# dmx_splitter.net
KiCad netlist of a schematic drawn in EAGLE
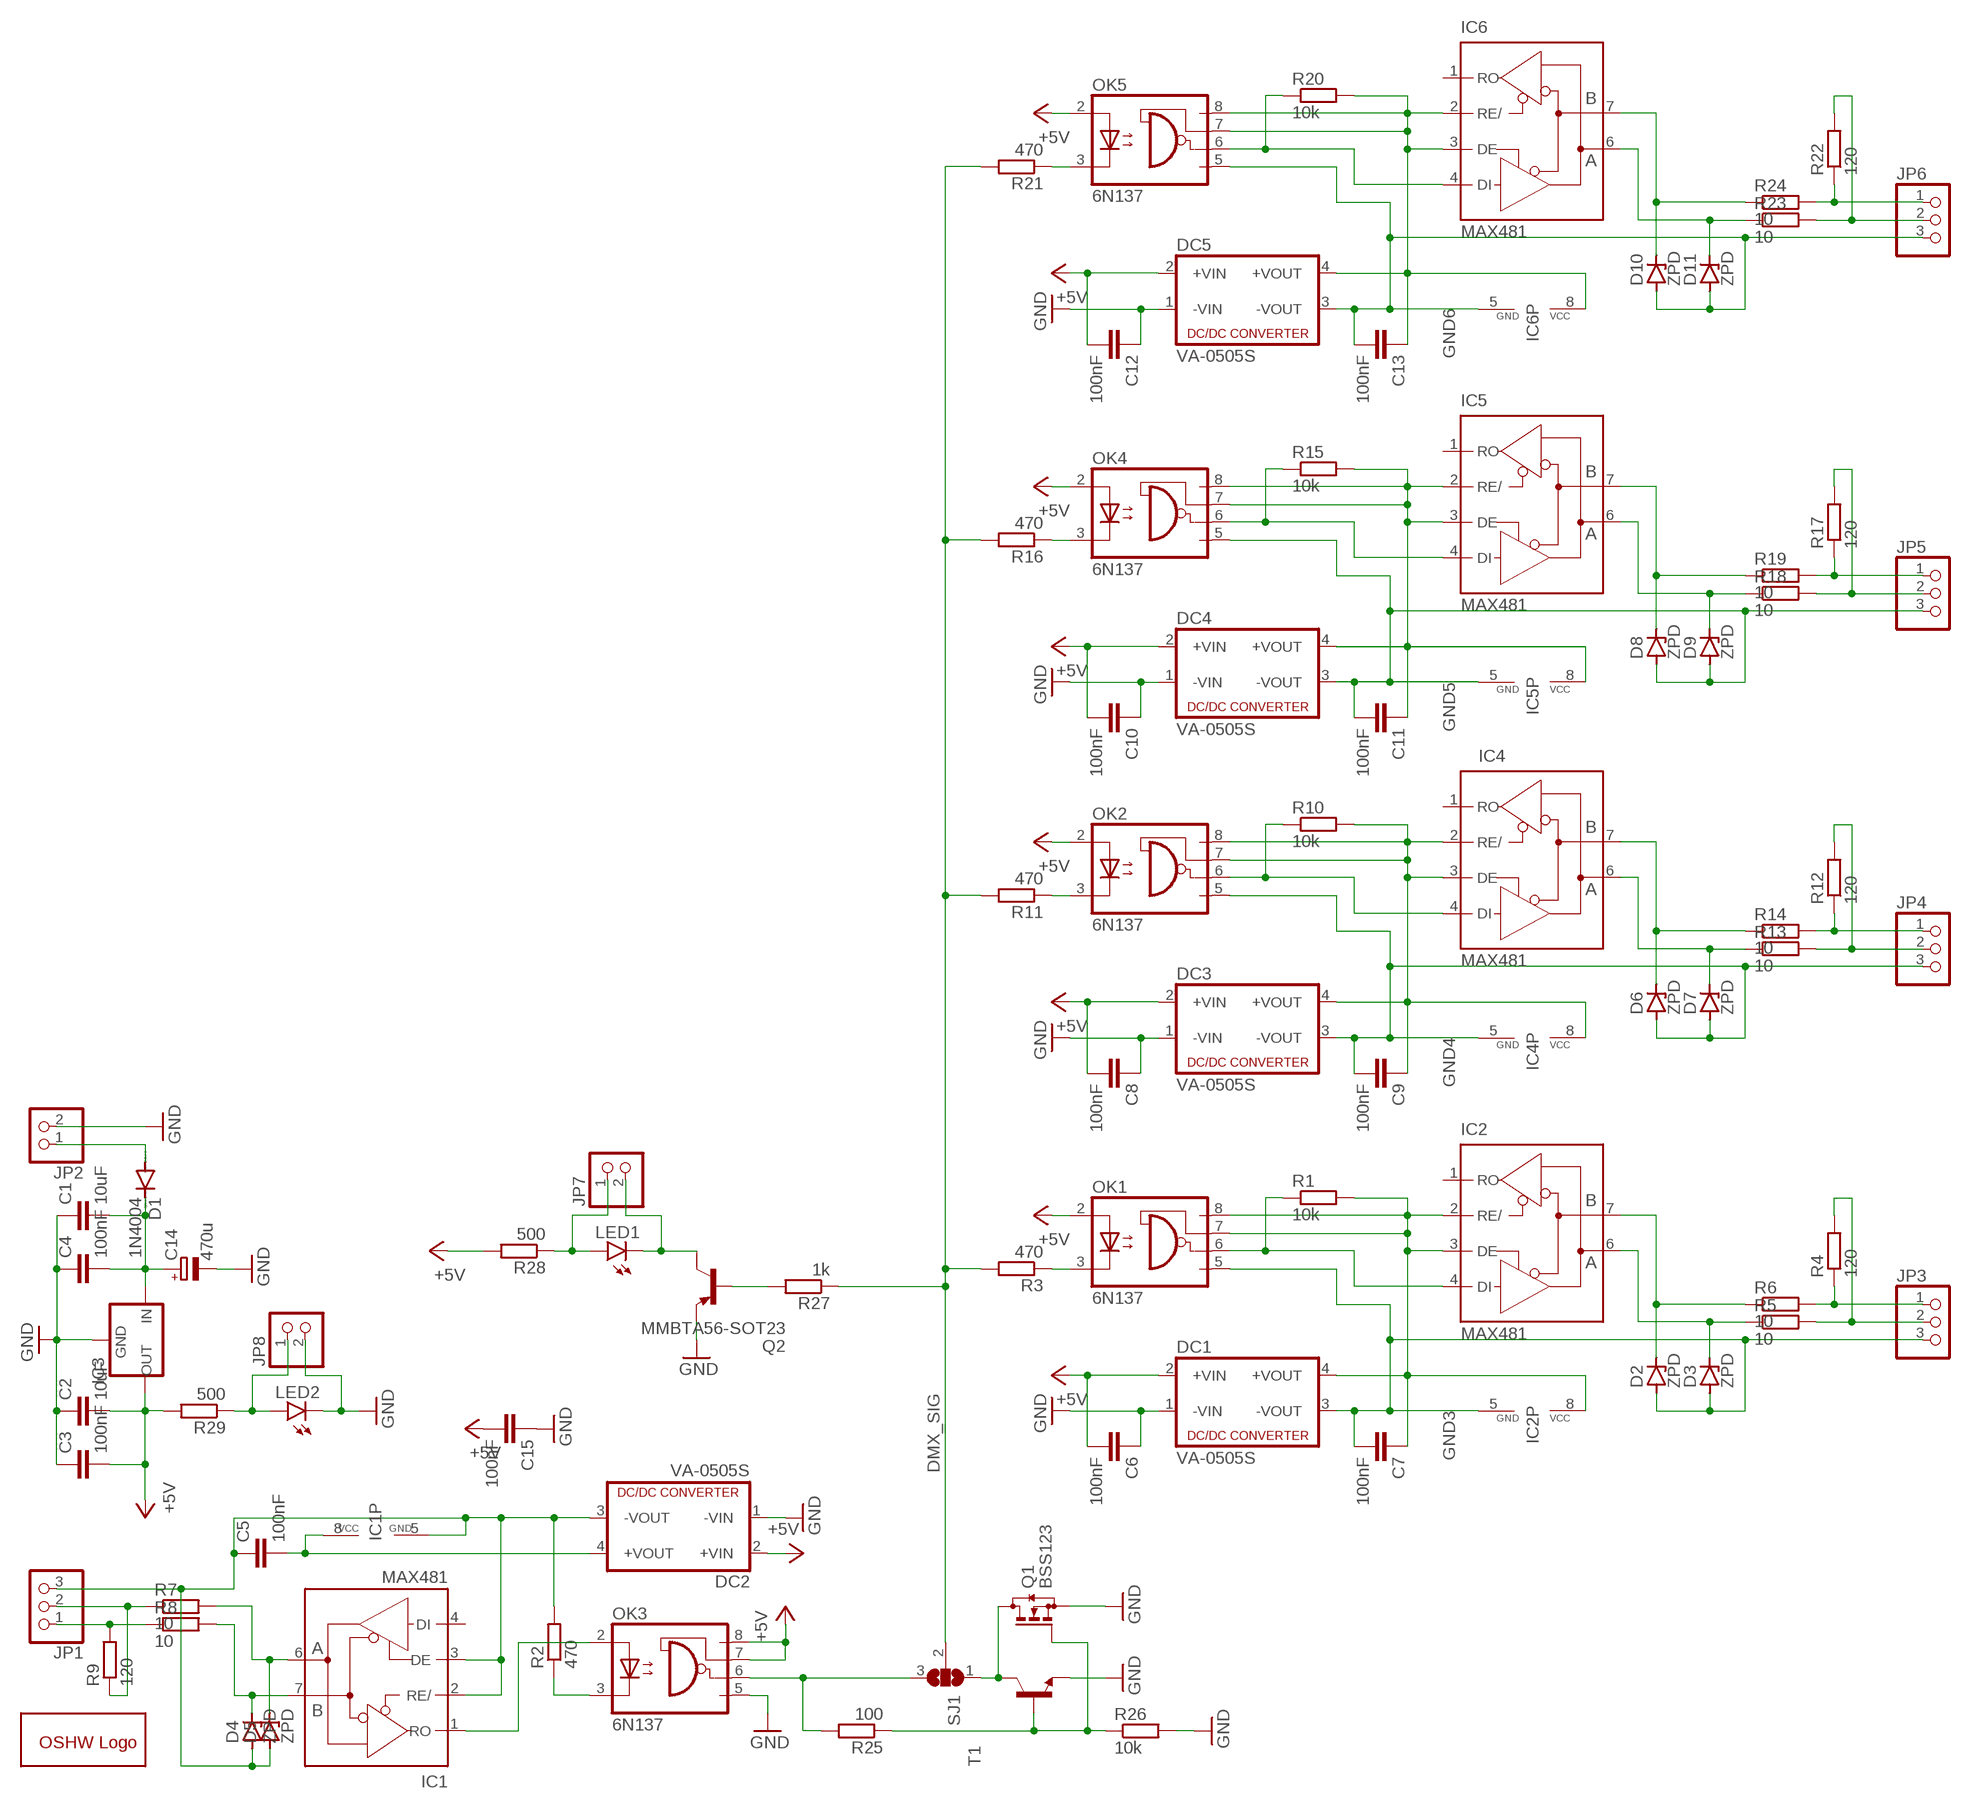
[diagram p0: schematic, sheet 1]

(export (version "E")
  (design (tool "Eeschema 10.0.6"))
  (components
    (comp (ref "C1")
      (value "10uF")
      (footprint "eagle-import:C1206")
      (libsource (lib "eagle-import") (part "C-EUC1206"))
    )
    (comp (ref "C2")
      (value "10uF")
      (footprint "eagle-import:C1206")
      (libsource (lib "eagle-import") (part "C-EUC1206"))
    )
    (comp (ref "C3")
      (value "100nF")
      (footprint "eagle-import:C1206")
      (libsource (lib "eagle-import") (part "C-EUC1206"))
    )
    (comp (ref "C4")
      (value "100nF")
      (footprint "eagle-import:C1206")
      (libsource (lib "eagle-import") (part "C-EUC1206"))
    )
    (comp (ref "C5")
      (value "100nF")
      (footprint "eagle-import:C1206")
      (libsource (lib "eagle-import") (part "C-EUC1206"))
    )
    (comp (ref "C6")
      (value "100nF")
      (footprint "eagle-import:C1206")
      (libsource (lib "eagle-import") (part "C-EUC1206"))
    )
    (comp (ref "C7")
      (value "100nF")
      (footprint "eagle-import:C1206")
      (libsource (lib "eagle-import") (part "C-EUC1206"))
    )
    (comp (ref "C8")
      (value "100nF")
      (footprint "eagle-import:C1206")
      (libsource (lib "eagle-import") (part "C-EUC1206"))
    )
    (comp (ref "C9")
      (value "100nF")
      (footprint "eagle-import:C1206")
      (libsource (lib "eagle-import") (part "C-EUC1206"))
    )
    (comp (ref "C10")
      (value "100nF")
      (footprint "eagle-import:C1206")
      (libsource (lib "eagle-import") (part "C-EUC1206"))
    )
    (comp (ref "C11")
      (value "100nF")
      (footprint "eagle-import:C1206")
      (libsource (lib "eagle-import") (part "C-EUC1206"))
    )
    (comp (ref "C12")
      (value "100nF")
      (footprint "eagle-import:C1206")
      (libsource (lib "eagle-import") (part "C-EUC1206"))
    )
    (comp (ref "C13")
      (value "100nF")
      (footprint "eagle-import:C1206")
      (libsource (lib "eagle-import") (part "C-EUC1206"))
    )
    (comp (ref "C14")
      (value "470u")
      (footprint "eagle-import:E2,5-7")
      (libsource (lib "eagle-import") (part "CPOL-EUE2.5-7"))
    )
    (comp (ref "C15")
      (value "100nF")
      (footprint "eagle-import:C1206")
      (libsource (lib "eagle-import") (part "C-EUC1206"))
    )
    (comp (ref "D1")
      (value "1N4004")
      (footprint "eagle-import:DO41-10")
      (libsource (lib "eagle-import") (part "1N4004"))
    )
    (comp (ref "D2")
      (value "ZPD")
      (footprint "eagle-import:DO35Z10")
      (libsource (lib "eagle-import") (part "ZPD"))
    )
    (comp (ref "D3")
      (value "ZPD")
      (footprint "eagle-import:DO35Z10")
      (libsource (lib "eagle-import") (part "ZPD"))
    )
    (comp (ref "D4")
      (value "ZPD")
      (footprint "eagle-import:DO35Z10")
      (libsource (lib "eagle-import") (part "ZPD"))
    )
    (comp (ref "D5")
      (value "ZPD")
      (footprint "eagle-import:DO35Z10")
      (libsource (lib "eagle-import") (part "ZPD"))
    )
    (comp (ref "D6")
      (value "ZPD")
      (footprint "eagle-import:DO35Z10")
      (libsource (lib "eagle-import") (part "ZPD"))
    )
    (comp (ref "D7")
      (value "ZPD")
      (footprint "eagle-import:DO35Z10")
      (libsource (lib "eagle-import") (part "ZPD"))
    )
    (comp (ref "D8")
      (value "ZPD")
      (footprint "eagle-import:DO35Z10")
      (libsource (lib "eagle-import") (part "ZPD"))
    )
    (comp (ref "D9")
      (value "ZPD")
      (footprint "eagle-import:DO35Z10")
      (libsource (lib "eagle-import") (part "ZPD"))
    )
    (comp (ref "D10")
      (value "ZPD")
      (footprint "eagle-import:DO35Z10")
      (libsource (lib "eagle-import") (part "ZPD"))
    )
    (comp (ref "D11")
      (value "ZPD")
      (footprint "eagle-import:DO35Z10")
      (libsource (lib "eagle-import") (part "ZPD"))
    )
    (comp (ref "DC1")
      (value "VA-0505S")
      (footprint "eagle-import:4SIL")
      (libsource (lib "eagle-import") (part "VA-?S0505"))
    )
    (comp (ref "DC2")
      (value "VA-0505S")
      (footprint "eagle-import:4SIL")
      (libsource (lib "eagle-import") (part "VA-?S0505"))
    )
    (comp (ref "DC3")
      (value "VA-0505S")
      (footprint "eagle-import:4SIL")
      (libsource (lib "eagle-import") (part "VA-?S0505"))
    )
    (comp (ref "DC4")
      (value "VA-0505S")
      (footprint "eagle-import:4SIL")
      (libsource (lib "eagle-import") (part "VA-?S0505"))
    )
    (comp (ref "DC5")
      (value "VA-0505S")
      (footprint "eagle-import:4SIL")
      (libsource (lib "eagle-import") (part "VA-?S0505"))
    )
    (comp (ref "GOLD_ORB_SM1")
      (value "OSHWLOGOLOGO5MM")
      (footprint "eagle-import:OSHW_5MM")
      (libsource (lib "eagle-import") (part "OSHWLOGOLOGO5MM"))
    )
    (comp (ref "IC1")
      (value "MAX481")
      (footprint "eagle-import:DIL08")
      (libsource (lib "eagle-import") (part "MAX481CPA"))
    )
    (comp (ref "IC2")
      (value "MAX481")
      (footprint "eagle-import:DIL08")
      (libsource (lib "eagle-import") (part "MAX481CPA"))
    )
    (comp (ref "IC3")
      (value "78XXS")
      (footprint "eagle-import:78XXS")
      (libsource (lib "eagle-import") (part "78XXS"))
    )
    (comp (ref "IC4")
      (value "MAX481")
      (footprint "eagle-import:DIL08")
      (libsource (lib "eagle-import") (part "MAX481CPA"))
    )
    (comp (ref "IC5")
      (value "MAX481")
      (footprint "eagle-import:DIL08")
      (libsource (lib "eagle-import") (part "MAX481CPA"))
    )
    (comp (ref "IC6")
      (value "MAX481")
      (footprint "eagle-import:DIL08")
      (libsource (lib "eagle-import") (part "MAX481CPA"))
    )
    (comp (ref "JP1")
      (value "PINHD-1X3")
      (footprint "eagle-import:1X03")
      (libsource (lib "eagle-import") (part "PINHD-1X3"))
    )
    (comp (ref "JP2")
      (value "PINHD-1X2")
      (footprint "eagle-import:1X02")
      (libsource (lib "eagle-import") (part "PINHD-1X2"))
    )
    (comp (ref "JP3")
      (value "PINHD-1X3")
      (footprint "eagle-import:1X03")
      (libsource (lib "eagle-import") (part "PINHD-1X3"))
    )
    (comp (ref "JP4")
      (value "PINHD-1X3")
      (footprint "eagle-import:1X03")
      (libsource (lib "eagle-import") (part "PINHD-1X3"))
    )
    (comp (ref "JP5")
      (value "PINHD-1X3")
      (footprint "eagle-import:1X03")
      (libsource (lib "eagle-import") (part "PINHD-1X3"))
    )
    (comp (ref "JP6")
      (value "PINHD-1X3")
      (footprint "eagle-import:1X03")
      (libsource (lib "eagle-import") (part "PINHD-1X3"))
    )
    (comp (ref "JP7")
      (value "PINHD-1X2")
      (footprint "eagle-import:1X02")
      (libsource (lib "eagle-import") (part "PINHD-1X2"))
    )
    (comp (ref "JP8")
      (value "PINHD-1X2")
      (footprint "eagle-import:1X02")
      (libsource (lib "eagle-import") (part "PINHD-1X2"))
    )
    (comp (ref "LED1")
      (value "LEDCHIPLED_1206")
      (footprint "eagle-import:CHIPLED_1206")
      (libsource (lib "eagle-import") (part "LEDCHIPLED_1206"))
    )
    (comp (ref "LED2")
      (value "LEDCHIPLED_1206")
      (footprint "eagle-import:CHIPLED_1206")
      (libsource (lib "eagle-import") (part "LEDCHIPLED_1206"))
    )
    (comp (ref "OK1")
      (value "6N137")
      (footprint "eagle-import:DIL08")
      (libsource (lib "eagle-import") (part "6N137"))
    )
    (comp (ref "OK2")
      (value "6N137")
      (footprint "eagle-import:DIL08")
      (libsource (lib "eagle-import") (part "6N137"))
    )
    (comp (ref "OK3")
      (value "6N137")
      (footprint "eagle-import:DIL08")
      (libsource (lib "eagle-import") (part "6N137"))
    )
    (comp (ref "OK4")
      (value "6N137")
      (footprint "eagle-import:DIL08")
      (libsource (lib "eagle-import") (part "6N137"))
    )
    (comp (ref "OK5")
      (value "6N137")
      (footprint "eagle-import:DIL08")
      (libsource (lib "eagle-import") (part "6N137"))
    )
    (comp (ref "Q1")
      (value "BSS123")
      (footprint "eagle-import:SOT23")
      (libsource (lib "eagle-import") (part "BSS123"))
    )
    (comp (ref "Q2")
      (value "MMBTA56-SOT23")
      (footprint "eagle-import:SOT23")
      (libsource (lib "eagle-import") (part "-?SOT23MMBTA56"))
    )
    (comp (ref "R1")
      (value "10k")
      (footprint "eagle-import:R1206")
      (libsource (lib "eagle-import") (part "R-EU_R1206"))
    )
    (comp (ref "R2")
      (value "470")
      (footprint "eagle-import:R1206")
      (libsource (lib "eagle-import") (part "R-EU_R1206"))
    )
    (comp (ref "R3")
      (value "470")
      (footprint "eagle-import:R1206")
      (libsource (lib "eagle-import") (part "R-EU_R1206"))
    )
    (comp (ref "R4")
      (value "120")
      (footprint "eagle-import:R1206")
      (libsource (lib "eagle-import") (part "R-EU_R1206"))
    )
    (comp (ref "R5")
      (value "10")
      (footprint "eagle-import:R1206")
      (libsource (lib "eagle-import") (part "R-EU_R1206"))
    )
    (comp (ref "R6")
      (value "10")
      (footprint "eagle-import:R1206")
      (libsource (lib "eagle-import") (part "R-EU_R1206"))
    )
    (comp (ref "R7")
      (value "10")
      (footprint "eagle-import:R1206")
      (libsource (lib "eagle-import") (part "R-EU_R1206"))
    )
    (comp (ref "R8")
      (value "10")
      (footprint "eagle-import:R1206")
      (libsource (lib "eagle-import") (part "R-EU_R1206"))
    )
    (comp (ref "R9")
      (value "120")
      (footprint "eagle-import:R1206")
      (libsource (lib "eagle-import") (part "R-EU_R1206"))
    )
    (comp (ref "R10")
      (value "10k")
      (footprint "eagle-import:R1206")
      (libsource (lib "eagle-import") (part "R-EU_R1206"))
    )
    (comp (ref "R11")
      (value "470")
      (footprint "eagle-import:R1206")
      (libsource (lib "eagle-import") (part "R-EU_R1206"))
    )
    (comp (ref "R12")
      (value "120")
      (footprint "eagle-import:R1206")
      (libsource (lib "eagle-import") (part "R-EU_R1206"))
    )
    (comp (ref "R13")
      (value "10")
      (footprint "eagle-import:R1206")
      (libsource (lib "eagle-import") (part "R-EU_R1206"))
    )
    (comp (ref "R14")
      (value "10")
      (footprint "eagle-import:R1206")
      (libsource (lib "eagle-import") (part "R-EU_R1206"))
    )
    (comp (ref "R15")
      (value "10k")
      (footprint "eagle-import:R1206")
      (libsource (lib "eagle-import") (part "R-EU_R1206"))
    )
    (comp (ref "R16")
      (value "470")
      (footprint "eagle-import:R1206")
      (libsource (lib "eagle-import") (part "R-EU_R1206"))
    )
    (comp (ref "R17")
      (value "120")
      (footprint "eagle-import:R1206")
      (libsource (lib "eagle-import") (part "R-EU_R1206"))
    )
    (comp (ref "R18")
      (value "10")
      (footprint "eagle-import:R1206")
      (libsource (lib "eagle-import") (part "R-EU_R1206"))
    )
    (comp (ref "R19")
      (value "10")
      (footprint "eagle-import:R1206")
      (libsource (lib "eagle-import") (part "R-EU_R1206"))
    )
    (comp (ref "R20")
      (value "10k")
      (footprint "eagle-import:R1206")
      (libsource (lib "eagle-import") (part "R-EU_R1206"))
    )
    (comp (ref "R21")
      (value "470")
      (footprint "eagle-import:R1206")
      (libsource (lib "eagle-import") (part "R-EU_R1206"))
    )
    (comp (ref "R22")
      (value "120")
      (footprint "eagle-import:R1206")
      (libsource (lib "eagle-import") (part "R-EU_R1206"))
    )
    (comp (ref "R23")
      (value "10")
      (footprint "eagle-import:R1206")
      (libsource (lib "eagle-import") (part "R-EU_R1206"))
    )
    (comp (ref "R24")
      (value "10")
      (footprint "eagle-import:R1206")
      (libsource (lib "eagle-import") (part "R-EU_R1206"))
    )
    (comp (ref "R25")
      (value "100")
      (footprint "eagle-import:R1206")
      (libsource (lib "eagle-import") (part "R-EU_R1206"))
    )
    (comp (ref "R26")
      (value "10k")
      (footprint "eagle-import:R1206")
      (libsource (lib "eagle-import") (part "R-EU_R1206"))
    )
    (comp (ref "R27")
      (value "1k")
      (footprint "eagle-import:R1206")
      (libsource (lib "eagle-import") (part "R-EU_R1206"))
    )
    (comp (ref "R28")
      (value "500")
      (footprint "eagle-import:R1206")
      (libsource (lib "eagle-import") (part "R-EU_R1206"))
    )
    (comp (ref "R29")
      (value "500")
      (footprint "eagle-import:R1206")
      (libsource (lib "eagle-import") (part "R-EU_R1206"))
    )
    (comp (ref "SJ1")
      (value "SJ2W")
      (footprint "eagle-import:SJ_2")
      (libsource (lib "eagle-import") (part "SJ2W"))
    )
    (comp (ref "T1")
      (value "-NPN-SOT23-EBC")
      (footprint "eagle-import:SOT23-EBC")
      (libsource (lib "eagle-import") (part "-NPN-SOT23-EBC"))
    )
  )
  (nets
    (net (code "1") (name "+5V") (class "Default")
      (node (ref "C10") (pin "2") (pinfunction "2_2") (pintype "passive"))
      (node (ref "C12") (pin "2") (pinfunction "2_2") (pintype "passive"))
      (node (ref "C15") (pin "2") (pinfunction "2_2") (pintype "passive"))
      (node (ref "C2") (pin "2") (pinfunction "2_2") (pintype "passive"))
      (node (ref "C3") (pin "2") (pinfunction "2_2") (pintype "passive"))
      (node (ref "C6") (pin "2") (pinfunction "2_2") (pintype "passive"))
      (node (ref "C8") (pin "2") (pinfunction "2_2") (pintype "passive"))
      (node (ref "DC1") (pin "2") (pinfunction "+VIN_2") (pintype "passive"))
      (node (ref "DC2") (pin "2") (pinfunction "+VIN_2") (pintype "passive"))
      (node (ref "DC3") (pin "2") (pinfunction "+VIN_2") (pintype "passive"))
      (node (ref "DC4") (pin "2") (pinfunction "+VIN_2") (pintype "passive"))
      (node (ref "DC5") (pin "2") (pinfunction "+VIN_2") (pintype "passive"))
      (node (ref "IC3") (pin "OUT") (pinfunction "OUT_OUT") (pintype "passive"))
      (node (ref "OK1") (pin "2") (pinfunction "A_2") (pintype "passive"))
      (node (ref "OK2") (pin "2") (pinfunction "A_2") (pintype "passive"))
      (node (ref "OK3") (pin "7") (pinfunction "VE_7") (pintype "passive"))
      (node (ref "OK3") (pin "8") (pinfunction "VCC_8") (pintype "passive"))
      (node (ref "OK4") (pin "2") (pinfunction "A_2") (pintype "passive"))
      (node (ref "OK5") (pin "2") (pinfunction "A_2") (pintype "passive"))
      (node (ref "R28") (pin "2") (pinfunction "2_2") (pintype "passive"))
      (node (ref "R29") (pin "2") (pinfunction "2_2") (pintype "passive"))
    )
    (net (code "2") (name "/DMX_SIG") (class "Default")
      (node (ref "R11") (pin "2") (pinfunction "2_2") (pintype "passive"))
      (node (ref "R16") (pin "2") (pinfunction "2_2") (pintype "passive"))
      (node (ref "R21") (pin "2") (pinfunction "2_2") (pintype "passive"))
      (node (ref "R27") (pin "1") (pinfunction "1_1") (pintype "passive"))
      (node (ref "R3") (pin "2") (pinfunction "2_2") (pintype "passive"))
      (node (ref "SJ1") (pin "2") (pinfunction "2_2") (pintype "passive"))
    )
    (net (code "3") (name "/GND3") (class "Default")
      (node (ref "C7") (pin "2") (pinfunction "2_2") (pintype "passive"))
      (node (ref "D2") (pin "A") (pinfunction "A_A") (pintype "passive"))
      (node (ref "D3") (pin "A") (pinfunction "A_A") (pintype "passive"))
      (node (ref "DC1") (pin "3") (pinfunction "-VOUT_3") (pintype "passive"))
      (node (ref "IC2") (pin "5") (pinfunction "GND_5") (pintype "power_in"))
      (node (ref "JP3") (pin "3") (pinfunction "3_3") (pintype "passive"))
      (node (ref "OK1") (pin "5") (pinfunction "GND_5") (pintype "passive"))
    )
    (net (code "4") (name "/GND4") (class "Default")
      (node (ref "C9") (pin "2") (pinfunction "2_2") (pintype "passive"))
      (node (ref "D6") (pin "A") (pinfunction "A_A") (pintype "passive"))
      (node (ref "D7") (pin "A") (pinfunction "A_A") (pintype "passive"))
      (node (ref "DC3") (pin "3") (pinfunction "-VOUT_3") (pintype "passive"))
      (node (ref "IC4") (pin "5") (pinfunction "GND_5") (pintype "power_in"))
      (node (ref "JP4") (pin "3") (pinfunction "3_3") (pintype "passive"))
      (node (ref "OK2") (pin "5") (pinfunction "GND_5") (pintype "passive"))
    )
    (net (code "5") (name "/GND5") (class "Default")
      (node (ref "C11") (pin "2") (pinfunction "2_2") (pintype "passive"))
      (node (ref "D8") (pin "A") (pinfunction "A_A") (pintype "passive"))
      (node (ref "D9") (pin "A") (pinfunction "A_A") (pintype "passive"))
      (node (ref "DC4") (pin "3") (pinfunction "-VOUT_3") (pintype "passive"))
      (node (ref "IC5") (pin "5") (pinfunction "GND_5") (pintype "power_in"))
      (node (ref "JP5") (pin "3") (pinfunction "3_3") (pintype "passive"))
      (node (ref "OK4") (pin "5") (pinfunction "GND_5") (pintype "passive"))
    )
    (net (code "6") (name "/GND6") (class "Default")
      (node (ref "C13") (pin "2") (pinfunction "2_2") (pintype "passive"))
      (node (ref "D10") (pin "A") (pinfunction "A_A") (pintype "passive"))
      (node (ref "D11") (pin "A") (pinfunction "A_A") (pintype "passive"))
      (node (ref "DC5") (pin "3") (pinfunction "-VOUT_3") (pintype "passive"))
      (node (ref "IC6") (pin "5") (pinfunction "GND_5") (pintype "power_in"))
      (node (ref "JP6") (pin "3") (pinfunction "3_3") (pintype "passive"))
      (node (ref "OK5") (pin "5") (pinfunction "GND_5") (pintype "passive"))
    )
    (net (code "7") (name "GND") (class "Default")
      (node (ref "C1") (pin "1") (pinfunction "1_1") (pintype "passive"))
      (node (ref "C10") (pin "1") (pinfunction "1_1") (pintype "passive"))
      (node (ref "C12") (pin "1") (pinfunction "1_1") (pintype "passive"))
      (node (ref "C14") (pin "-") (pinfunction "-_-") (pintype "passive"))
      (node (ref "C15") (pin "1") (pinfunction "1_1") (pintype "passive"))
      (node (ref "C2") (pin "1") (pinfunction "1_1") (pintype "passive"))
      (node (ref "C3") (pin "1") (pinfunction "1_1") (pintype "passive"))
      (node (ref "C4") (pin "1") (pinfunction "1_1") (pintype "passive"))
      (node (ref "C6") (pin "1") (pinfunction "1_1") (pintype "passive"))
      (node (ref "C8") (pin "1") (pinfunction "1_1") (pintype "passive"))
      (node (ref "DC1") (pin "1") (pinfunction "-VIN_1") (pintype "passive"))
      (node (ref "DC2") (pin "1") (pinfunction "-VIN_1") (pintype "passive"))
      (node (ref "DC3") (pin "1") (pinfunction "-VIN_1") (pintype "passive"))
      (node (ref "DC4") (pin "1") (pinfunction "-VIN_1") (pintype "passive"))
      (node (ref "DC5") (pin "1") (pinfunction "-VIN_1") (pintype "passive"))
      (node (ref "IC3") (pin "GND") (pinfunction "GND_GND") (pintype "input"))
      (node (ref "JP2") (pin "2") (pinfunction "2_2") (pintype "passive"))
      (node (ref "JP8") (pin "2") (pinfunction "2_2") (pintype "passive"))
      (node (ref "LED2") (pin "C") (pinfunction "C_C") (pintype "passive"))
      (node (ref "OK3") (pin "5") (pinfunction "GND_5") (pintype "passive"))
      (node (ref "Q1") (pin "2") (pinfunction "S_2") (pintype "passive"))
      (node (ref "Q2") (pin "2") (pinfunction "E_2") (pintype "passive"))
      (node (ref "R26") (pin "2") (pinfunction "2_2") (pintype "passive"))
      (node (ref "T1") (pin "E") (pinfunction "E_E") (pintype "passive"))
    )
    (net (code "8") (name "Net-(C1-Pad2)") (class "Default")
      (node (ref "C1") (pin "2") (pinfunction "2_2") (pintype "passive"))
      (node (ref "C14") (pin "+") (pinfunction "+_+") (pintype "passive"))
      (node (ref "C4") (pin "2") (pinfunction "2_2") (pintype "passive"))
      (node (ref "D1") (pin "C") (pinfunction "C_C") (pintype "passive"))
      (node (ref "IC3") (pin "IN") (pinfunction "IN_IN") (pintype "input"))
    )
    (net (code "9") (name "Net-(D1-PadA)") (class "Default")
      (node (ref "D1") (pin "A") (pinfunction "A_A") (pintype "passive"))
      (node (ref "JP2") (pin "1") (pinfunction "1_1") (pintype "passive"))
    )
    (net (code "10") (name "Net-(DC1-+VOUT)") (class "Default")
      (node (ref "C7") (pin "1") (pinfunction "1_1") (pintype "passive"))
      (node (ref "DC1") (pin "4") (pinfunction "+VOUT_4") (pintype "passive"))
      (node (ref "IC2") (pin "2") (pinfunction "RE/_2") (pintype "input"))
      (node (ref "IC2") (pin "3") (pinfunction "DE_3") (pintype "input"))
      (node (ref "IC2") (pin "8") (pinfunction "VCC_8") (pintype "power_in"))
      (node (ref "OK1") (pin "7") (pinfunction "VE_7") (pintype "passive"))
      (node (ref "OK1") (pin "8") (pinfunction "VCC_8") (pintype "passive"))
      (node (ref "R1") (pin "2") (pinfunction "2_2") (pintype "passive"))
    )
    (net (code "11") (name "Net-(DC2-+VOUT)") (class "Default")
      (node (ref "C5") (pin "2") (pinfunction "2_2") (pintype "passive"))
      (node (ref "DC2") (pin "4") (pinfunction "+VOUT_4") (pintype "passive"))
      (node (ref "IC1") (pin "8") (pinfunction "VCC_8") (pintype "power_in"))
    )
    (net (code "12") (name "Net-(DC2--VOUT)") (class "Default")
      (node (ref "C5") (pin "1") (pinfunction "1_1") (pintype "passive"))
      (node (ref "D4") (pin "A") (pinfunction "A_A") (pintype "passive"))
      (node (ref "D5") (pin "A") (pinfunction "A_A") (pintype "passive"))
      (node (ref "DC2") (pin "3") (pinfunction "-VOUT_3") (pintype "passive"))
      (node (ref "IC1") (pin "2") (pinfunction "RE/_2") (pintype "input"))
      (node (ref "IC1") (pin "3") (pinfunction "DE_3") (pintype "input"))
      (node (ref "IC1") (pin "5") (pinfunction "GND_5") (pintype "power_in"))
      (node (ref "JP1") (pin "3") (pinfunction "3_3") (pintype "passive"))
      (node (ref "R2") (pin "2") (pinfunction "2_2") (pintype "passive"))
    )
    (net (code "13") (name "Net-(DC3-+VOUT)") (class "Default")
      (node (ref "C9") (pin "1") (pinfunction "1_1") (pintype "passive"))
      (node (ref "DC3") (pin "4") (pinfunction "+VOUT_4") (pintype "passive"))
      (node (ref "IC4") (pin "2") (pinfunction "RE/_2") (pintype "input"))
      (node (ref "IC4") (pin "3") (pinfunction "DE_3") (pintype "input"))
      (node (ref "IC4") (pin "8") (pinfunction "VCC_8") (pintype "power_in"))
      (node (ref "OK2") (pin "7") (pinfunction "VE_7") (pintype "passive"))
      (node (ref "OK2") (pin "8") (pinfunction "VCC_8") (pintype "passive"))
      (node (ref "R10") (pin "2") (pinfunction "2_2") (pintype "passive"))
    )
    (net (code "14") (name "Net-(DC4-+VOUT)") (class "Default")
      (node (ref "C11") (pin "1") (pinfunction "1_1") (pintype "passive"))
      (node (ref "DC4") (pin "4") (pinfunction "+VOUT_4") (pintype "passive"))
      (node (ref "IC5") (pin "2") (pinfunction "RE/_2") (pintype "input"))
      (node (ref "IC5") (pin "3") (pinfunction "DE_3") (pintype "input"))
      (node (ref "IC5") (pin "8") (pinfunction "VCC_8") (pintype "power_in"))
      (node (ref "OK4") (pin "7") (pinfunction "VE_7") (pintype "passive"))
      (node (ref "OK4") (pin "8") (pinfunction "VCC_8") (pintype "passive"))
      (node (ref "R15") (pin "2") (pinfunction "2_2") (pintype "passive"))
    )
    (net (code "15") (name "Net-(DC5-+VOUT)") (class "Default")
      (node (ref "C13") (pin "1") (pinfunction "1_1") (pintype "passive"))
      (node (ref "DC5") (pin "4") (pinfunction "+VOUT_4") (pintype "passive"))
      (node (ref "IC6") (pin "2") (pinfunction "RE/_2") (pintype "input"))
      (node (ref "IC6") (pin "3") (pinfunction "DE_3") (pintype "input"))
      (node (ref "IC6") (pin "8") (pinfunction "VCC_8") (pintype "power_in"))
      (node (ref "OK5") (pin "7") (pinfunction "VE_7") (pintype "passive"))
      (node (ref "OK5") (pin "8") (pinfunction "VCC_8") (pintype "passive"))
      (node (ref "R20") (pin "2") (pinfunction "2_2") (pintype "passive"))
    )
    (net (code "16") (name "Net-(IC1A-A)") (class "Default")
      (node (ref "D5") (pin "C") (pinfunction "C_C") (pintype "passive"))
      (node (ref "IC1") (pin "6") (pinfunction "A_6") (pintype "passive"))
      (node (ref "R7") (pin "2") (pinfunction "2_2") (pintype "passive"))
    )
    (net (code "17") (name "Net-(IC1A-B)") (class "Default")
      (node (ref "D4") (pin "C") (pinfunction "C_C") (pintype "passive"))
      (node (ref "IC1") (pin "7") (pinfunction "B_7") (pintype "passive"))
      (node (ref "R8") (pin "2") (pinfunction "2_2") (pintype "passive"))
    )
    (net (code "18") (name "Net-(IC1A-RO)") (class "Default")
      (node (ref "IC1") (pin "1") (pinfunction "RO_1") (pintype "output"))
      (node (ref "OK3") (pin "2") (pinfunction "A_2") (pintype "passive"))
    )
    (net (code "19") (name "Net-(IC2A-A)") (class "Default")
      (node (ref "D3") (pin "C") (pinfunction "C_C") (pintype "passive"))
      (node (ref "IC2") (pin "6") (pinfunction "A_6") (pintype "passive"))
      (node (ref "R5") (pin "1") (pinfunction "1_1") (pintype "passive"))
    )
    (net (code "20") (name "Net-(IC2A-B)") (class "Default")
      (node (ref "D2") (pin "C") (pinfunction "C_C") (pintype "passive"))
      (node (ref "IC2") (pin "7") (pinfunction "B_7") (pintype "passive"))
      (node (ref "R6") (pin "1") (pinfunction "1_1") (pintype "passive"))
    )
    (net (code "21") (name "Net-(IC2A-DI)") (class "Default")
      (node (ref "IC2") (pin "4") (pinfunction "DI_4") (pintype "input"))
      (node (ref "OK1") (pin "6") (pinfunction "VO_6") (pintype "passive"))
      (node (ref "R1") (pin "1") (pinfunction "1_1") (pintype "passive"))
    )
    (net (code "22") (name "Net-(IC4A-A)") (class "Default")
      (node (ref "D7") (pin "C") (pinfunction "C_C") (pintype "passive"))
      (node (ref "IC4") (pin "6") (pinfunction "A_6") (pintype "passive"))
      (node (ref "R13") (pin "1") (pinfunction "1_1") (pintype "passive"))
    )
    (net (code "23") (name "Net-(IC4A-B)") (class "Default")
      (node (ref "D6") (pin "C") (pinfunction "C_C") (pintype "passive"))
      (node (ref "IC4") (pin "7") (pinfunction "B_7") (pintype "passive"))
      (node (ref "R14") (pin "1") (pinfunction "1_1") (pintype "passive"))
    )
    (net (code "24") (name "Net-(IC4A-DI)") (class "Default")
      (node (ref "IC4") (pin "4") (pinfunction "DI_4") (pintype "input"))
      (node (ref "OK2") (pin "6") (pinfunction "VO_6") (pintype "passive"))
      (node (ref "R10") (pin "1") (pinfunction "1_1") (pintype "passive"))
    )
    (net (code "25") (name "Net-(IC5A-A)") (class "Default")
      (node (ref "D9") (pin "C") (pinfunction "C_C") (pintype "passive"))
      (node (ref "IC5") (pin "6") (pinfunction "A_6") (pintype "passive"))
      (node (ref "R18") (pin "1") (pinfunction "1_1") (pintype "passive"))
    )
    (net (code "26") (name "Net-(IC5A-B)") (class "Default")
      (node (ref "D8") (pin "C") (pinfunction "C_C") (pintype "passive"))
      (node (ref "IC5") (pin "7") (pinfunction "B_7") (pintype "passive"))
      (node (ref "R19") (pin "1") (pinfunction "1_1") (pintype "passive"))
    )
    (net (code "27") (name "Net-(IC5A-DI)") (class "Default")
      (node (ref "IC5") (pin "4") (pinfunction "DI_4") (pintype "input"))
      (node (ref "OK4") (pin "6") (pinfunction "VO_6") (pintype "passive"))
      (node (ref "R15") (pin "1") (pinfunction "1_1") (pintype "passive"))
    )
    (net (code "28") (name "Net-(IC6A-A)") (class "Default")
      (node (ref "D11") (pin "C") (pinfunction "C_C") (pintype "passive"))
      (node (ref "IC6") (pin "6") (pinfunction "A_6") (pintype "passive"))
      (node (ref "R23") (pin "1") (pinfunction "1_1") (pintype "passive"))
    )
    (net (code "29") (name "Net-(IC6A-B)") (class "Default")
      (node (ref "D10") (pin "C") (pinfunction "C_C") (pintype "passive"))
      (node (ref "IC6") (pin "7") (pinfunction "B_7") (pintype "passive"))
      (node (ref "R24") (pin "1") (pinfunction "1_1") (pintype "passive"))
    )
    (net (code "30") (name "Net-(IC6A-DI)") (class "Default")
      (node (ref "IC6") (pin "4") (pinfunction "DI_4") (pintype "input"))
      (node (ref "OK5") (pin "6") (pinfunction "VO_6") (pintype "passive"))
      (node (ref "R20") (pin "1") (pinfunction "1_1") (pintype "passive"))
    )
    (net (code "31") (name "Net-(JP1-Pad1)") (class "Default")
      (node (ref "JP1") (pin "1") (pinfunction "1_1") (pintype "passive"))
      (node (ref "R8") (pin "1") (pinfunction "1_1") (pintype "passive"))
      (node (ref "R9") (pin "2") (pinfunction "2_2") (pintype "passive"))
    )
    (net (code "32") (name "Net-(JP1-Pad2)") (class "Default")
      (node (ref "JP1") (pin "2") (pinfunction "2_2") (pintype "passive"))
      (node (ref "R7") (pin "1") (pinfunction "1_1") (pintype "passive"))
      (node (ref "R9") (pin "1") (pinfunction "1_1") (pintype "passive"))
    )
    (net (code "33") (name "Net-(JP3-Pad1)") (class "Default")
      (node (ref "JP3") (pin "1") (pinfunction "1_1") (pintype "passive"))
      (node (ref "R4") (pin "1") (pinfunction "1_1") (pintype "passive"))
      (node (ref "R6") (pin "2") (pinfunction "2_2") (pintype "passive"))
    )
    (net (code "34") (name "Net-(JP3-Pad2)") (class "Default")
      (node (ref "JP3") (pin "2") (pinfunction "2_2") (pintype "passive"))
      (node (ref "R4") (pin "2") (pinfunction "2_2") (pintype "passive"))
      (node (ref "R5") (pin "2") (pinfunction "2_2") (pintype "passive"))
    )
    (net (code "35") (name "Net-(JP4-Pad1)") (class "Default")
      (node (ref "JP4") (pin "1") (pinfunction "1_1") (pintype "passive"))
      (node (ref "R12") (pin "1") (pinfunction "1_1") (pintype "passive"))
      (node (ref "R14") (pin "2") (pinfunction "2_2") (pintype "passive"))
    )
    (net (code "36") (name "Net-(JP4-Pad2)") (class "Default")
      (node (ref "JP4") (pin "2") (pinfunction "2_2") (pintype "passive"))
      (node (ref "R12") (pin "2") (pinfunction "2_2") (pintype "passive"))
      (node (ref "R13") (pin "2") (pinfunction "2_2") (pintype "passive"))
    )
    (net (code "37") (name "Net-(JP5-Pad1)") (class "Default")
      (node (ref "JP5") (pin "1") (pinfunction "1_1") (pintype "passive"))
      (node (ref "R17") (pin "1") (pinfunction "1_1") (pintype "passive"))
      (node (ref "R19") (pin "2") (pinfunction "2_2") (pintype "passive"))
    )
    (net (code "38") (name "Net-(JP5-Pad2)") (class "Default")
      (node (ref "JP5") (pin "2") (pinfunction "2_2") (pintype "passive"))
      (node (ref "R17") (pin "2") (pinfunction "2_2") (pintype "passive"))
      (node (ref "R18") (pin "2") (pinfunction "2_2") (pintype "passive"))
    )
    (net (code "39") (name "Net-(JP6-Pad1)") (class "Default")
      (node (ref "JP6") (pin "1") (pinfunction "1_1") (pintype "passive"))
      (node (ref "R22") (pin "1") (pinfunction "1_1") (pintype "passive"))
      (node (ref "R24") (pin "2") (pinfunction "2_2") (pintype "passive"))
    )
    (net (code "40") (name "Net-(JP6-Pad2)") (class "Default")
      (node (ref "JP6") (pin "2") (pinfunction "2_2") (pintype "passive"))
      (node (ref "R22") (pin "2") (pinfunction "2_2") (pintype "passive"))
      (node (ref "R23") (pin "2") (pinfunction "2_2") (pintype "passive"))
    )
    (net (code "41") (name "Net-(JP7-Pad1)") (class "Default")
      (node (ref "JP7") (pin "1") (pinfunction "1_1") (pintype "passive"))
      (node (ref "LED1") (pin "A") (pinfunction "A_A") (pintype "passive"))
      (node (ref "R28") (pin "1") (pinfunction "1_1") (pintype "passive"))
    )
    (net (code "42") (name "Net-(JP8-Pad1)") (class "Default")
      (node (ref "JP8") (pin "1") (pinfunction "1_1") (pintype "passive"))
      (node (ref "LED2") (pin "A") (pinfunction "A_A") (pintype "passive"))
      (node (ref "R29") (pin "1") (pinfunction "1_1") (pintype "passive"))
    )
    (net (code "43") (name "Net-(OK1-C)") (class "Default")
      (node (ref "OK1") (pin "3") (pinfunction "C_3") (pintype "passive"))
      (node (ref "R3") (pin "1") (pinfunction "1_1") (pintype "passive"))
    )
    (net (code "44") (name "Net-(OK2-C)") (class "Default")
      (node (ref "OK2") (pin "3") (pinfunction "C_3") (pintype "passive"))
      (node (ref "R11") (pin "1") (pinfunction "1_1") (pintype "passive"))
    )
    (net (code "45") (name "Net-(OK3-C)") (class "Default")
      (node (ref "OK3") (pin "3") (pinfunction "C_3") (pintype "passive"))
      (node (ref "R2") (pin "1") (pinfunction "1_1") (pintype "passive"))
    )
    (net (code "46") (name "Net-(OK3-VO)") (class "Default")
      (node (ref "OK3") (pin "6") (pinfunction "VO_6") (pintype "passive"))
      (node (ref "R25") (pin "2") (pinfunction "2_2") (pintype "passive"))
      (node (ref "SJ1") (pin "3") (pinfunction "3_3") (pintype "passive"))
    )
    (net (code "47") (name "Net-(OK4-C)") (class "Default")
      (node (ref "OK4") (pin "3") (pinfunction "C_3") (pintype "passive"))
      (node (ref "R16") (pin "1") (pinfunction "1_1") (pintype "passive"))
    )
    (net (code "48") (name "Net-(OK5-C)") (class "Default")
      (node (ref "OK5") (pin "3") (pinfunction "C_3") (pintype "passive"))
      (node (ref "R21") (pin "1") (pinfunction "1_1") (pintype "passive"))
    )
    (net (code "49") (name "Net-(Q1-D)") (class "Default")
      (node (ref "Q1") (pin "3") (pinfunction "D_3") (pintype "passive"))
      (node (ref "SJ1") (pin "1") (pinfunction "1_1") (pintype "passive"))
      (node (ref "T1") (pin "C") (pinfunction "C_C") (pintype "passive"))
    )
    (net (code "50") (name "Net-(Q1-G)") (class "Default")
      (node (ref "Q1") (pin "1") (pinfunction "G_1") (pintype "passive"))
      (node (ref "R25") (pin "1") (pinfunction "1_1") (pintype "passive"))
      (node (ref "R26") (pin "1") (pinfunction "1_1") (pintype "passive"))
      (node (ref "T1") (pin "B") (pinfunction "B_B") (pintype "passive"))
    )
    (net (code "51") (name "Net-(Q2-B)") (class "Default")
      (node (ref "Q2") (pin "1") (pinfunction "B_1") (pintype "passive"))
      (node (ref "R27") (pin "2") (pinfunction "2_2") (pintype "passive"))
    )
    (net (code "52") (name "Net-(Q2-C)") (class "Default")
      (node (ref "JP7") (pin "2") (pinfunction "2_2") (pintype "passive"))
      (node (ref "LED1") (pin "C") (pinfunction "C_C") (pintype "passive"))
      (node (ref "Q2") (pin "3") (pinfunction "C_3") (pintype "passive"))
    )
    (net (code "53") (name "unconnected-(IC1A-DI-Pad4)") (class "Default")
      (node (ref "IC1") (pin "4") (pinfunction "DI_4") (pintype "input"))
    )
    (net (code "54") (name "unconnected-(IC2A-RO-Pad1)") (class "Default")
      (node (ref "IC2") (pin "1") (pinfunction "RO_1") (pintype "output"))
    )
    (net (code "55") (name "unconnected-(IC4A-RO-Pad1)") (class "Default")
      (node (ref "IC4") (pin "1") (pinfunction "RO_1") (pintype "output"))
    )
    (net (code "56") (name "unconnected-(IC5A-RO-Pad1)") (class "Default")
      (node (ref "IC5") (pin "1") (pinfunction "RO_1") (pintype "output"))
    )
    (net (code "57") (name "unconnected-(IC6A-RO-Pad1)") (class "Default")
      (node (ref "IC6") (pin "1") (pinfunction "RO_1") (pintype "output"))
    )
  )
)
